# Agrobot_1_1.net
KiCad netlist of a schematic drawn in Altium Designer
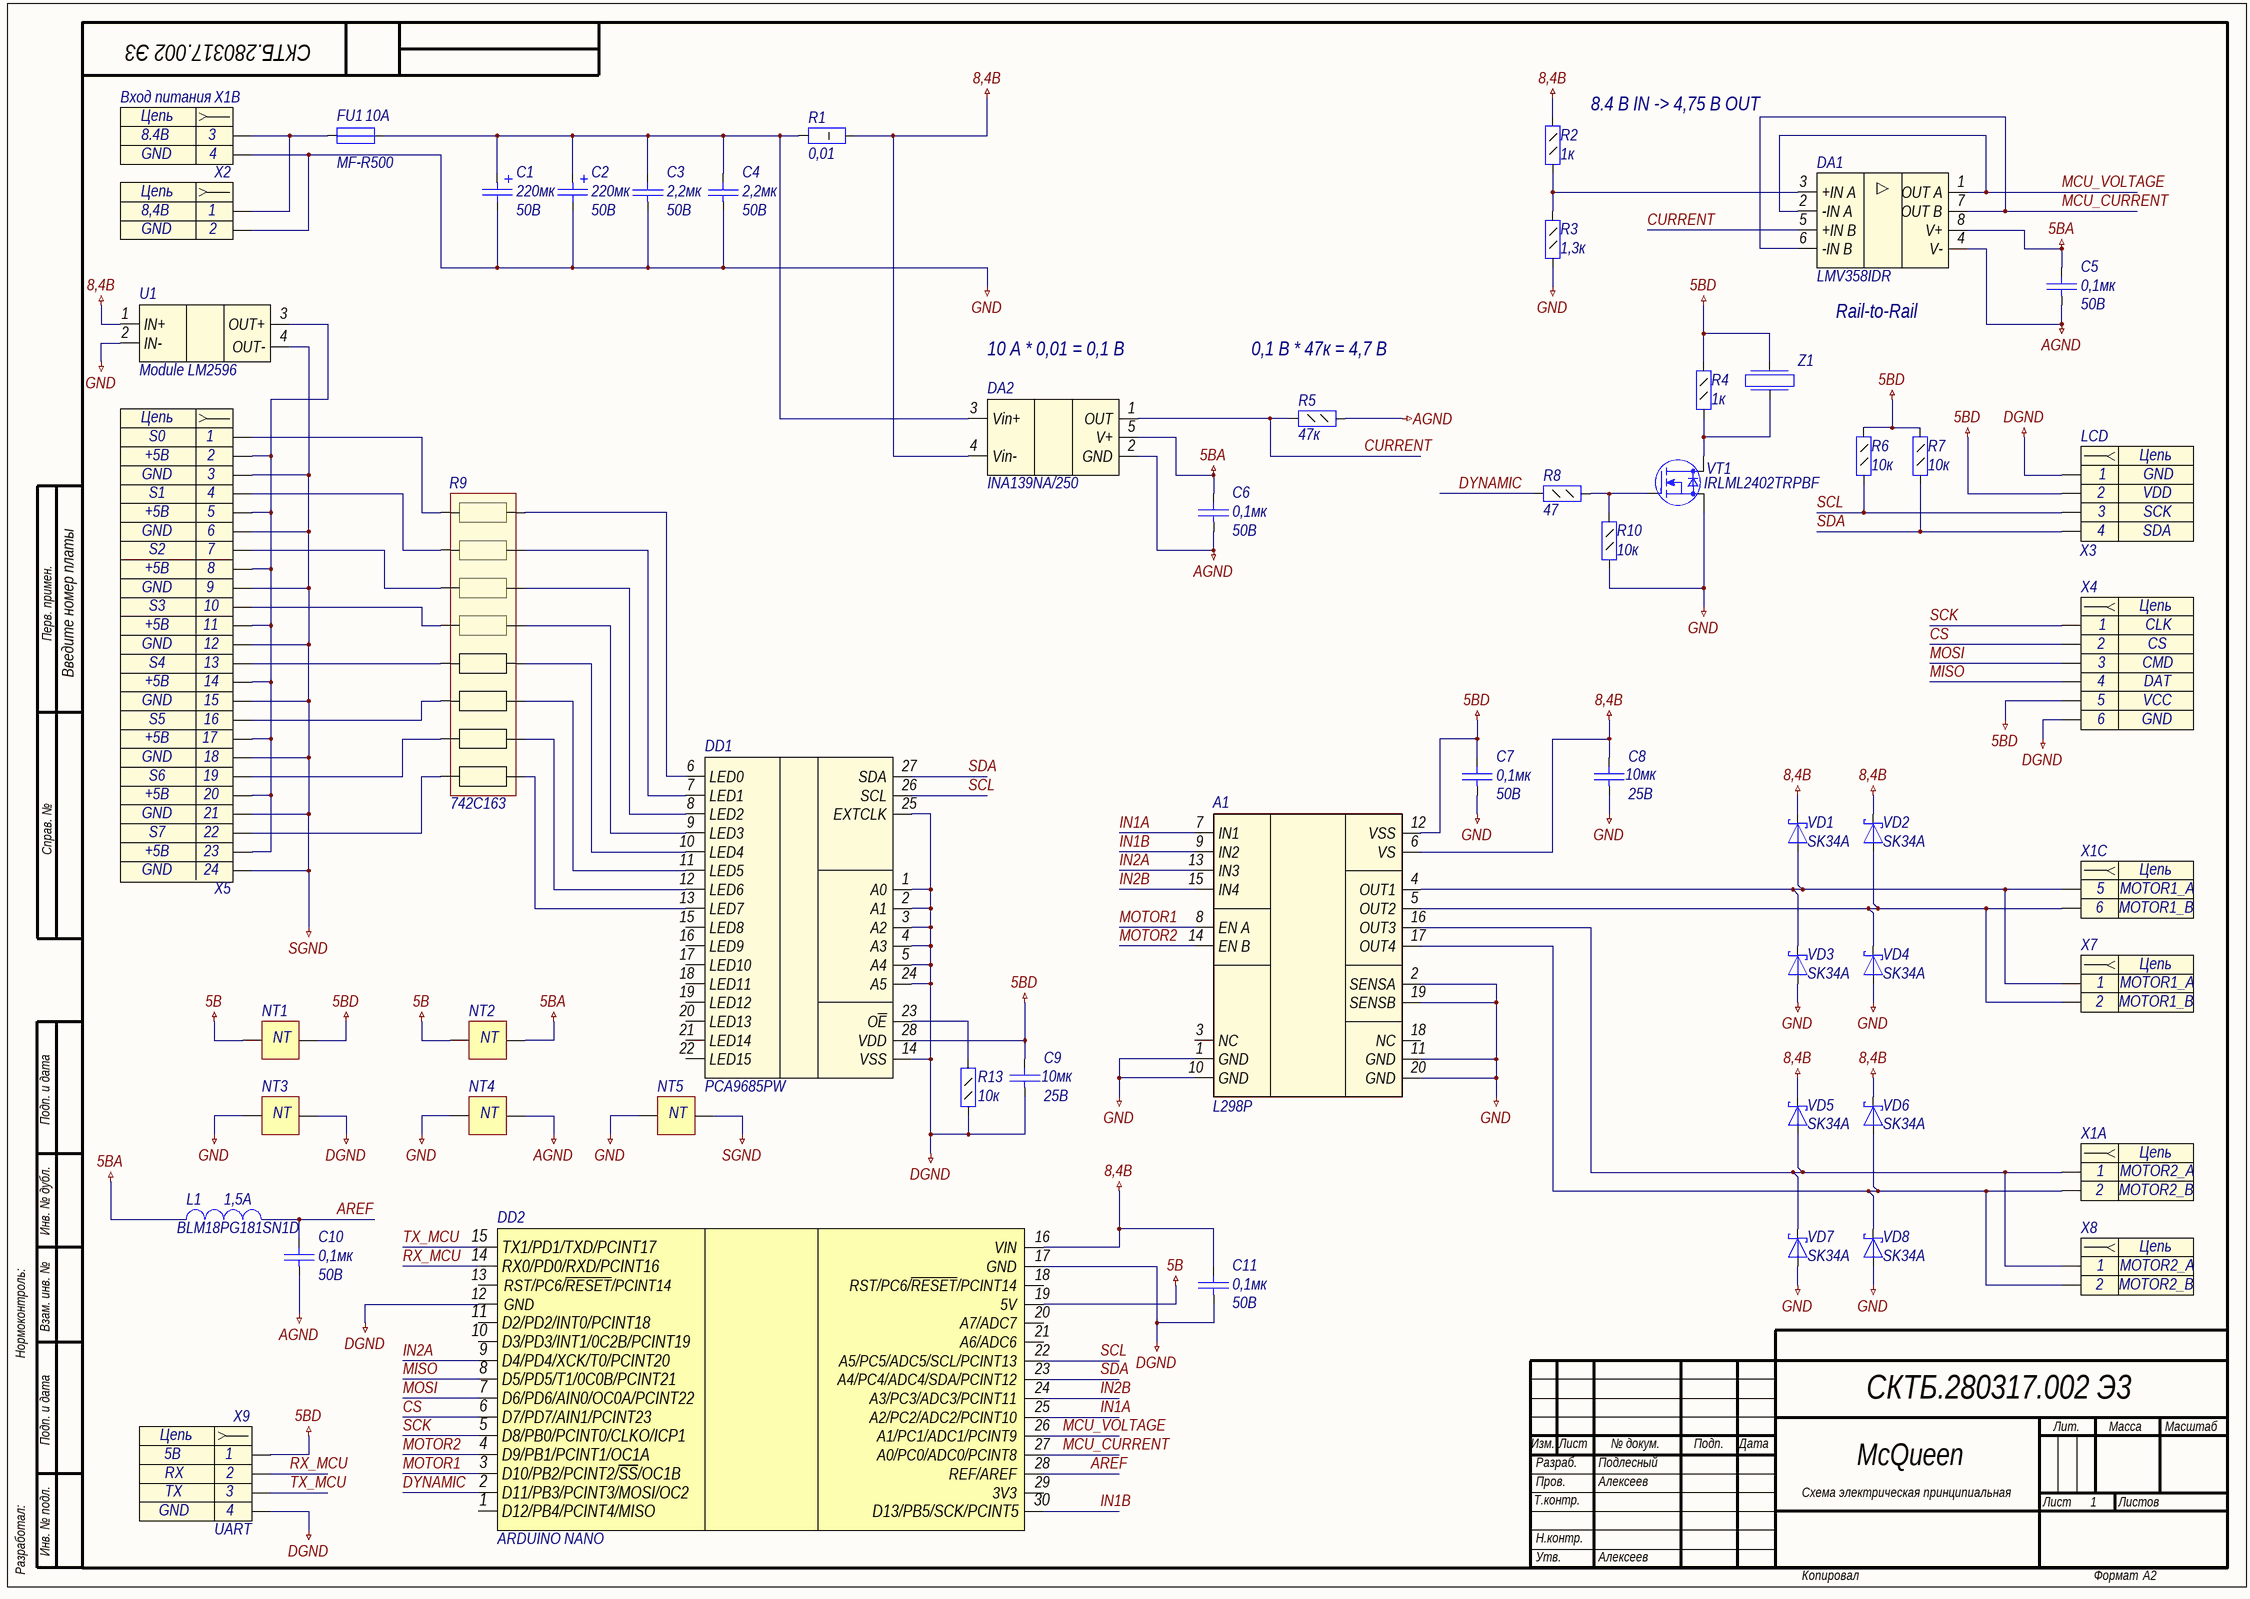
[diagram p0: Agrobot_1.1.SchDoc]

(export (version "E")
  (design (tool "Eeschema 10.0.6"))
  (components
    (comp (ref "A1")
      (value "L298P")
      (footprint "POWERSO20")
      (description "FULL BRIDGE DC MOTOR DRIVER")
      (libsource (lib "MOP44") (part "L298P"))
    )
    (comp (ref "C1")
      (value "220мк")
      (footprint "Cap_SMD_radial_polar(10x10.5)")
      (description "Конденсатор полярный")
      (fields
        (field (name "VOLTAGE") "50В")
        (field (name "PART NUMBER") "ECAP SMD")
        (field (name "Comment") "Capacitor_pol")
      )
      (libsource (lib "MOP44") (part "Capacitor_pol"))
    )
    (comp (ref "C2")
      (value "220мк")
      (footprint "Cap_SMD_radial_polar(10x10.5)")
      (description "Конденсатор полярный")
      (fields
        (field (name "VOLTAGE") "50В")
        (field (name "PART NUMBER") "ECAP SMD")
        (field (name "Comment") "Capacitor_pol")
      )
      (libsource (lib "MOP44") (part "Capacitor_pol"))
    )
    (comp (ref "C3")
      (value "2,2мк")
      (footprint "C0805")
      (description "Конденсатор")
      (fields
        (field (name "VOLTAGE") "50B")
        (field (name "PART NUMBER") "GRM21BR71E225K")
        (field (name "Comment") "Capacitor")
      )
      (libsource (lib "MOP44") (part "Capacitor"))
    )
    (comp (ref "C4")
      (value "2,2мк")
      (footprint "C0805")
      (description "Конденсатор")
      (fields
        (field (name "VOLTAGE") "50B")
        (field (name "PART NUMBER") "GRM21BR71E225K")
        (field (name "Comment") "Capacitor")
      )
      (libsource (lib "MOP44") (part "Capacitor"))
    )
    (comp (ref "C5")
      (value "0,1мк")
      (footprint "C0805")
      (description "Конденсатор")
      (fields
        (field (name "VOLTAGE") "50B")
        (field (name "PART NUMBER") "GRM21BR71E225K")
        (field (name "Comment") "Capacitor")
      )
      (libsource (lib "MOP44") (part "Capacitor"))
    )
    (comp (ref "C6")
      (value "0,1мк")
      (footprint "C0805")
      (description "Конденсатор")
      (fields
        (field (name "VOLTAGE") "50B")
        (field (name "PART NUMBER") "GRM21BR71E225K")
        (field (name "Comment") "Capacitor")
      )
      (libsource (lib "MOP44") (part "Capacitor"))
    )
    (comp (ref "C7")
      (value "0,1мк")
      (footprint "C0805")
      (description "Конденсатор")
      (fields
        (field (name "VOLTAGE") "50B")
        (field (name "PART NUMBER") "GRM21BR71E225K")
        (field (name "Comment") "Capacitor")
      )
      (libsource (lib "MOP44") (part "Capacitor"))
    )
    (comp (ref "C8")
      (value "10мк")
      (footprint "C1210")
      (description "Конденсатор")
      (fields
        (field (name "VOLTAGE") "25В")
        (field (name "PART NUMBER") "GRM32ER61A106K")
        (field (name "Comment") "Capacitor")
      )
      (libsource (lib "MOP44") (part "Capacitor"))
    )
    (comp (ref "C9")
      (value "10мк")
      (footprint "C1210")
      (description "Конденсатор")
      (fields
        (field (name "VOLTAGE") "25В")
        (field (name "PART NUMBER") "GRM32ER61A106K")
        (field (name "Comment") "Capacitor")
      )
      (libsource (lib "MOP44") (part "Capacitor"))
    )
    (comp (ref "C10")
      (value "0,1мк")
      (footprint "C0805")
      (description "Конденсатор")
      (fields
        (field (name "VOLTAGE") "50B")
        (field (name "PART NUMBER") "GRM21BR71E225K")
        (field (name "Comment") "Capacitor")
      )
      (libsource (lib "MOP44") (part "Capacitor"))
    )
    (comp (ref "C11")
      (value "0,1мк")
      (footprint "C0805")
      (description "Конденсатор")
      (fields
        (field (name "VOLTAGE") "50B")
        (field (name "PART NUMBER") "GRM21BR71E225K")
        (field (name "Comment") "Capacitor")
      )
      (libsource (lib "MOP44") (part "Capacitor"))
    )
    (comp (ref "DA1")
      (value "LMV358IDR")
      (footprint "SO8")
      (description "LOW-VOLTAGE RAIL-TO-RAIL OUTPUT OPERATIONAL AMPLIFIERS")
      (libsource (lib "MOP44") (part "LMV358IDR"))
    )
    (comp (ref "DA2")
      (value "INA139NA/250")
      (footprint "SOT23-5")
      (description "Измерительный датчик тока")
      (libsource (lib "MOP44") (part "INA139NA/250"))
    )
    (comp (ref "DD1")
      (value "PCA9685PW")
      (footprint "TSSOP28")
      (description "Драйвер светодиода, 16 выходов")
      (libsource (lib "MOP44") (part "PCA9685PW"))
    )
    (comp (ref "DD2")
      (value "ARDUINO NANO")
      (footprint "ARDUINO NANO")
      (description "Отладочная плата ATmega328")
      (libsource (lib "MOP44") (part "ARDUINO NANO"))
    )
    (comp (ref "FU1")
      (value "Fuse")
      (footprint "MF-R500")
      (description "Предохранитель")
      (fields (field (name "I TRIP") "10A") (field (name "PART NUMBER") "MF-R500"))
      (libsource (lib "MOP44") (part "Fuse"))
    )
    (comp (ref "L1")
      (value "Inductor")
      (footprint "L0603")
      (description "EMI Suppression Filter")
      (fields (field (name "PART NUMBER") "BLM18PG181SN1D") (field (name "RATED CURRENT") "1,5A"))
      (libsource (lib "MOP44") (part "Inductor"))
    )
    (comp (ref "NT1")
      (value "Pofigistor")
      (footprint "Pofigistor0603")
      (libsource (lib "MOP44") (part "Pofigistor"))
    )
    (comp (ref "NT2")
      (value "Pofigistor")
      (footprint "Pofigistor0603")
      (libsource (lib "MOP44") (part "Pofigistor"))
    )
    (comp (ref "NT3")
      (value "Pofigistor")
      (footprint "Pofigistor0603")
      (libsource (lib "MOP44") (part "Pofigistor"))
    )
    (comp (ref "NT4")
      (value "Pofigistor")
      (footprint "Pofigistor0603")
      (libsource (lib "MOP44") (part "Pofigistor"))
    )
    (comp (ref "NT5")
      (value "Pofigistor")
      (footprint "Pofigistor0603")
      (libsource (lib "MOP44") (part "Pofigistor"))
    )
    (comp (ref "R1")
      (value "0,01")
      (footprint "R2512")
      (description "Резистор")
      (fields (field (name "POWER") "1Вт") (field (name "Comment") "Resistor_1Вт"))
      (libsource (lib "MOP44") (part "Resistor_1Вт"))
    )
    (comp (ref "R2")
      (value "1к")
      (footprint "R0805")
      (description "Резистор")
      (fields (field (name "POWER") "0,125Вт") (field (name "Comment") "Resistor_0,125Вт"))
      (libsource (lib "MOP44") (part "Resistor_0,125Вт"))
    )
    (comp (ref "R3")
      (value "1,3к")
      (footprint "R0805")
      (description "Резистор")
      (fields (field (name "POWER") "0,125Вт") (field (name "Comment") "Resistor_0,125Вт"))
      (libsource (lib "MOP44") (part "Resistor_0,125Вт"))
    )
    (comp (ref "R4")
      (value "1к")
      (footprint "R0805")
      (description "Резистор")
      (fields (field (name "POWER") "0,125Вт") (field (name "Comment") "Resistor_0,125Вт"))
      (libsource (lib "MOP44") (part "Resistor_0,125Вт"))
    )
    (comp (ref "R5")
      (value "47к")
      (footprint "R0805")
      (description "Резистор")
      (fields (field (name "POWER") "0,125Вт") (field (name "Comment") "Resistor_0,125Вт"))
      (libsource (lib "") (part "Resistor_0,125Вт_1"))
    )
    (comp (ref "R6")
      (value "10к")
      (footprint "R0805")
      (description "Резистор")
      (fields (field (name "POWER") "0,125Вт") (field (name "Comment") "Resistor_0,125Вт"))
      (libsource (lib "MOP44") (part "Resistor_0,125Вт"))
    )
    (comp (ref "R7")
      (value "10к")
      (footprint "R0805")
      (description "Резистор")
      (fields (field (name "POWER") "0,125Вт") (field (name "Comment") "Resistor_0,125Вт"))
      (libsource (lib "MOP44") (part "Resistor_0,125Вт"))
    )
    (comp (ref "R8")
      (value "47")
      (footprint "R0805")
      (description "Резистор")
      (fields (field (name "POWER") "0,125Вт") (field (name "Comment") "Resistor_0,125Вт"))
      (libsource (lib "") (part "Resistor_0,125Вт_1"))
    )
    (comp (ref "R9")
      (value "742C163")
      (footprint "ZabugorLib:8xR1206")
      (description "Резисторная сборка")
      (libsource (lib "MOP44") (part "742C163"))
    )
    (comp (ref "R10")
      (value "10к")
      (footprint "R0805")
      (description "Резистор")
      (fields (field (name "POWER") "0,125Вт") (field (name "Comment") "Resistor_0,125Вт"))
      (libsource (lib "MOP44") (part "Resistor_0,125Вт"))
    )
    (comp (ref "R13")
      (value "10к")
      (footprint "R0805")
      (description "Резистор")
      (fields (field (name "POWER") "0,125Вт") (field (name "Comment") "Resistor_0,125Вт"))
      (libsource (lib "") (part "Resistor_0,125Вт_2"))
    )
    (comp (ref "U1")
      (value "Module LM2596")
      (footprint "module LM2596")
      (description "Low-Dropout Regulator for 5-V to 3.3-V Conversion")
      (libsource (lib "MOP44") (part "Module LM2596"))
    )
    (comp (ref "VD1")
      (value "DiodeSchottky")
      (footprint "SMA")
      (description "Диод Шоттки")
      (fields (field (name "PART NUMBER") "SK34A"))
      (libsource (lib "MOP44") (part "DiodeSchottky"))
    )
    (comp (ref "VD2")
      (value "DiodeSchottky")
      (footprint "SMA")
      (description "Диод Шоттки")
      (fields (field (name "PART NUMBER") "SK34A"))
      (libsource (lib "MOP44") (part "DiodeSchottky"))
    )
    (comp (ref "VD3")
      (value "DiodeSchottky")
      (footprint "SMA")
      (description "Диод Шоттки")
      (fields (field (name "PART NUMBER") "SK34A"))
      (libsource (lib "MOP44") (part "DiodeSchottky"))
    )
    (comp (ref "VD4")
      (value "DiodeSchottky")
      (footprint "SMA")
      (description "Диод Шоттки")
      (fields (field (name "PART NUMBER") "SK34A"))
      (libsource (lib "MOP44") (part "DiodeSchottky"))
    )
    (comp (ref "VD5")
      (value "DiodeSchottky")
      (footprint "SMA")
      (description "Диод Шоттки")
      (fields (field (name "PART NUMBER") "SK34A"))
      (libsource (lib "MOP44") (part "DiodeSchottky"))
    )
    (comp (ref "VD6")
      (value "DiodeSchottky")
      (footprint "SMA")
      (description "Диод Шоттки")
      (fields (field (name "PART NUMBER") "SK34A"))
      (libsource (lib "MOP44") (part "DiodeSchottky"))
    )
    (comp (ref "VD7")
      (value "DiodeSchottky")
      (footprint "SMA")
      (description "Диод Шоттки")
      (fields (field (name "PART NUMBER") "SK34A"))
      (libsource (lib "MOP44") (part "DiodeSchottky"))
    )
    (comp (ref "VD8")
      (value "DiodeSchottky")
      (footprint "SMA")
      (description "Диод Шоттки")
      (fields (field (name "PART NUMBER") "SK34A"))
      (libsource (lib "MOP44") (part "DiodeSchottky"))
    )
    (comp (ref "VT1")
      (value "N-MOSFET")
      (footprint "SOT23-3")
      (fields (field (name "PART NUMBER") "IRLML2402TRPBF"))
      (libsource (lib "MOP44") (part "N-MOSFET"))
    )
    (comp (ref "X1")
      (value "Вход питания")
      (footprint "ZabugorLib:DT-128V-6")
      (description "POWER")
      (libsource (lib "MOP44") (part "Header_6_motor"))
    )
    (comp (ref "X2")
      (value "Header_2_sct")
      (footprint "2HOLE_2.5")
      (description "Разъем - 2 конт. розетка")
      (libsource (lib "") (part "Header_2_sct_1"))
    )
    (comp (ref "X3")
      (value "LCD")
      (footprint "PLS-4HOLES")
      (description "Разъем - 4 конт. розетка")
      (libsource (lib "") (part "Header_4_sct_1"))
    )
    (comp (ref "X4")
      (value "Header_6_sct")
      (footprint "PSP_ANTENNA")
      (description "Разъем - 6 конт. розетка")
      (libsource (lib "MOP44") (part "Header_6_sct"))
    )
    (comp (ref "X5")
      (value "Header_24_sct")
      (footprint "PLS-24-3")
      (description "Разъем - 5 конт. розетка")
      (libsource (lib "MOP44") (part "Header_24_sct"))
    )
    (comp (ref "X7")
      (value "Header_2_sct")
      (footprint "2HOLE_2.5")
      (description "Разъем - 2 конт. розетка")
      (libsource (lib "MOP44") (part "Header_2_sct"))
    )
    (comp (ref "X8")
      (value "Header_2_sct")
      (footprint "2HOLE_2.5")
      (description "Разъем - 2 конт. розетка")
      (libsource (lib "MOP44") (part "Header_2_sct"))
    )
    (comp (ref "X9")
      (value "UART")
      (footprint "PLS-4HOLES")
      (description "Разъем - 4 конт. розетка")
      (libsource (lib "MOP44") (part "Header_4_sct"))
    )
    (comp (ref "Z1")
      (value "~")
      (footprint "Buzzer_9mm")
      (description "Пьезоизлучатель звуковой без генератора")
      (fields (field (name "PART NUMBER") "HC0905F"))
      (libsource (lib "MOP44") (part "Buzzer"))
    )
  )
  (nets
    (net (code "1") (name "/AREF") (class "Default")
      (node (ref "C10") (pin "2") (pinfunction "2_2") (pintype "passive"))
      (node (ref "DD2") (pin "28") (pinfunction "REF/AREF_28") (pintype "passive"))
      (node (ref "L1") (pin "2") (pinfunction "2_2") (pintype "passive"))
    )
    (net (code "2") (name "/CS") (class "Default")
      (node (ref "DD2") (pin "6") (pinfunction "D7/PD7/AIN1/PCINT23_6") (pintype "passive"))
      (node (ref "X4") (pin "2") (pinfunction "2_2") (pintype "passive"))
    )
    (net (code "3") (name "/CURRENT") (class "Default")
      (node (ref "DA1") (pin "5") (pinfunction "+IN_B_5") (pintype "passive"))
      (node (ref "DA2") (pin "1") (pinfunction "OUT_1") (pintype "power_in"))
      (node (ref "R5") (pin "2") (pinfunction "2_2") (pintype "passive"))
    )
    (net (code "4") (name "/DYNAMIC") (class "Default")
      (node (ref "DD2") (pin "2") (pinfunction "D11/PB3/PCINT3/MOSI/OC2_2") (pintype "passive"))
      (node (ref "R8") (pin "2") (pinfunction "2_2") (pintype "passive"))
    )
    (net (code "5") (name "/IN1A") (class "Default")
      (node (ref "A1") (pin "7") (pinfunction "IN1_7") (pintype "passive"))
      (node (ref "DD2") (pin "25") (pinfunction "A2/PC2/ADC2/PCINT10_25") (pintype "passive"))
    )
    (net (code "6") (name "/IN1B") (class "Default")
      (node (ref "A1") (pin "9") (pinfunction "IN2_9") (pintype "passive"))
      (node (ref "DD2") (pin "30") (pinfunction "D13/PB5/SCK/PCINT5_30") (pintype "passive"))
    )
    (net (code "7") (name "/IN2A") (class "Default")
      (node (ref "A1") (pin "13") (pinfunction "IN3_13") (pintype "passive"))
      (node (ref "DD2") (pin "9") (pinfunction "D4/PD4/XCK/T0/PCINT20_9") (pintype "passive"))
    )
    (net (code "8") (name "/IN2B") (class "Default")
      (node (ref "A1") (pin "15") (pinfunction "IN4_15") (pintype "passive"))
      (node (ref "DD2") (pin "24") (pinfunction "A3/PC3/ADC3/PCINT11_24") (pintype "passive"))
    )
    (net (code "9") (name "/MCU_CURRENT") (class "Default")
      (node (ref "DA1") (pin "6") (pinfunction "-IN_B_6") (pintype "passive"))
      (node (ref "DA1") (pin "7") (pinfunction "OUT_B_7") (pintype "passive"))
      (node (ref "DD2") (pin "27") (pinfunction "A0/PC0/ADC0/PCINT8_27") (pintype "passive"))
    )
    (net (code "10") (name "/MCU_VOLTAGE") (class "Default")
      (node (ref "DA1") (pin "1") (pinfunction "OUT_A_1") (pintype "passive"))
      (node (ref "DA1") (pin "2") (pinfunction "-IN_A_2") (pintype "passive"))
      (node (ref "DD2") (pin "26") (pinfunction "A1/PC1/ADC1/PCINT9_26") (pintype "passive"))
    )
    (net (code "11") (name "/MISO") (class "Default")
      (node (ref "DD2") (pin "8") (pinfunction "D5/PD5/T1/0C0B/PCINT21_8") (pintype "passive"))
      (node (ref "X4") (pin "4") (pinfunction "4_4") (pintype "passive"))
    )
    (net (code "12") (name "/MOSI") (class "Default")
      (node (ref "DD2") (pin "7") (pinfunction "D6/PD6/AIN0/OC0A/PCINT22_7") (pintype "passive"))
      (node (ref "X4") (pin "3") (pinfunction "3_3") (pintype "passive"))
    )
    (net (code "13") (name "/MOTOR1") (class "Default")
      (node (ref "A1") (pin "8") (pinfunction "EN_A_8") (pintype "passive"))
      (node (ref "DD2") (pin "3") (pinfunction "D10/PB2/PCINT2/~{SS}/OC1B_3") (pintype "passive"))
    )
    (net (code "14") (name "/MOTOR2") (class "Default")
      (node (ref "A1") (pin "14") (pinfunction "EN_B_14") (pintype "passive"))
      (node (ref "DD2") (pin "4") (pinfunction "D9/PB1/PCINT1/OC1A_4") (pintype "passive"))
    )
    (net (code "15") (name "/RX_MCU") (class "Default")
      (node (ref "DD2") (pin "14") (pinfunction "RX0/PD0/RXD/PCINT16_14") (pintype "passive"))
      (node (ref "X9") (pin "2") (pinfunction "2_2") (pintype "passive"))
    )
    (net (code "16") (name "/SCK") (class "Default")
      (node (ref "DD2") (pin "5") (pinfunction "D8/PB0/PCINT0/CLKO/ICP1_5") (pintype "passive"))
      (node (ref "X4") (pin "1") (pinfunction "1_1") (pintype "passive"))
    )
    (net (code "17") (name "/SCL") (class "Default")
      (node (ref "DD1") (pin "26") (pinfunction "SCL_26") (pintype "power_in"))
      (node (ref "DD2") (pin "22") (pinfunction "A5/PC5/ADC5/SCL/PCINT13_22") (pintype "passive"))
      (node (ref "R6") (pin "2") (pinfunction "2_2") (pintype "passive"))
      (node (ref "X3") (pin "3") (pinfunction "3_3") (pintype "passive"))
    )
    (net (code "18") (name "/SDA") (class "Default")
      (node (ref "DD1") (pin "27") (pinfunction "SDA_27") (pintype "power_in"))
      (node (ref "DD2") (pin "23") (pinfunction "A4/PC4/ADC4/SDA/PCINT12_23") (pintype "passive"))
      (node (ref "R7") (pin "2") (pinfunction "2_2") (pintype "passive"))
      (node (ref "X3") (pin "4") (pinfunction "4_4") (pintype "passive"))
    )
    (net (code "19") (name "/TX_MCU") (class "Default")
      (node (ref "DD2") (pin "15") (pinfunction "TX1/PD1/TXD/PCINT17_15") (pintype "passive"))
      (node (ref "X9") (pin "3") (pinfunction "3_3") (pintype "passive"))
    )
    (net (code "20") (name "5В") (class "Default")
      (node (ref "DD2") (pin "19") (pinfunction "5V_19") (pintype "passive"))
      (node (ref "NT1") (pin "1") (pinfunction "1_1") (pintype "passive"))
      (node (ref "NT2") (pin "1") (pinfunction "1_1") (pintype "passive"))
    )
    (net (code "21") (name "5ВA") (class "Default")
      (node (ref "C5") (pin "2") (pinfunction "2_2") (pintype "passive"))
      (node (ref "C6") (pin "2") (pinfunction "2_2") (pintype "passive"))
      (node (ref "DA1") (pin "8") (pinfunction "V+_8") (pintype "passive"))
      (node (ref "DA2") (pin "5") (pinfunction "V+_5") (pintype "power_in"))
      (node (ref "L1") (pin "1") (pinfunction "1_1") (pintype "passive"))
      (node (ref "NT2") (pin "2") (pinfunction "2_2") (pintype "passive"))
    )
    (net (code "22") (name "5ВD") (class "Default")
      (node (ref "A1") (pin "12") (pinfunction "VSS_12") (pintype "passive"))
      (node (ref "C7") (pin "2") (pinfunction "2_2") (pintype "passive"))
      (node (ref "C9") (pin "2") (pinfunction "2_2") (pintype "passive"))
      (node (ref "DD1") (pin "28") (pinfunction "VDD_28") (pintype "power_in"))
      (node (ref "NT1") (pin "2") (pinfunction "2_2") (pintype "passive"))
      (node (ref "R4") (pin "1") (pinfunction "1_1") (pintype "passive"))
      (node (ref "R6") (pin "1") (pinfunction "1_1") (pintype "passive"))
      (node (ref "R7") (pin "1") (pinfunction "1_1") (pintype "passive"))
      (node (ref "X3") (pin "2") (pinfunction "2_2") (pintype "passive"))
      (node (ref "X4") (pin "5") (pinfunction "5_5") (pintype "passive"))
      (node (ref "X9") (pin "1") (pinfunction "1_1") (pintype "passive"))
      (node (ref "Z1") (pin "2") (pinfunction "2_2") (pintype "passive"))
    )
    (net (code "23") (name "8,4В") (class "Default")
      (node (ref "A1") (pin "6") (pinfunction "VS_6") (pintype "passive"))
      (node (ref "C11") (pin "2") (pinfunction "2_2") (pintype "passive"))
      (node (ref "C8") (pin "2") (pinfunction "2_2") (pintype "passive"))
      (node (ref "DA2") (pin "4") (pinfunction "Vin-_4") (pintype "power_in"))
      (node (ref "DD2") (pin "16") (pinfunction "VIN_16") (pintype "passive"))
      (node (ref "R1") (pin "2") (pinfunction "5_2") (pintype "passive"))
      (node (ref "R2") (pin "1") (pinfunction "1_1") (pintype "passive"))
      (node (ref "U1") (pin "1") (pinfunction "IN+_1") (pintype "power_in"))
      (node (ref "VD1") (pin "1") (pinfunction "K_1") (pintype "passive"))
      (node (ref "VD2") (pin "1") (pinfunction "K_1") (pintype "passive"))
      (node (ref "VD5") (pin "1") (pinfunction "K_1") (pintype "passive"))
      (node (ref "VD6") (pin "1") (pinfunction "K_1") (pintype "passive"))
    )
    (net (code "24") (name "AGND") (class "Default")
      (node (ref "C10") (pin "1") (pinfunction "1_1") (pintype "passive"))
      (node (ref "C5") (pin "1") (pinfunction "1_1") (pintype "passive"))
      (node (ref "C6") (pin "1") (pinfunction "1_1") (pintype "passive"))
      (node (ref "DA1") (pin "4") (pinfunction "V-_4") (pintype "passive"))
      (node (ref "DA2") (pin "2") (pinfunction "GND_2") (pintype "power_in"))
      (node (ref "NT4") (pin "2") (pinfunction "2_2") (pintype "passive"))
      (node (ref "R5") (pin "1") (pinfunction "1_1") (pintype "passive"))
    )
    (net (code "25") (name "DGND") (class "Default")
      (node (ref "C11") (pin "1") (pinfunction "1_1") (pintype "passive"))
      (node (ref "C9") (pin "1") (pinfunction "1_1") (pintype "passive"))
      (node (ref "DD1") (pin "1") (pinfunction "A0_1") (pintype "power_in"))
      (node (ref "DD1") (pin "14") (pinfunction "VSS_14") (pintype "power_in"))
      (node (ref "DD1") (pin "2") (pinfunction "A1_2") (pintype "power_in"))
      (node (ref "DD1") (pin "24") (pinfunction "A5_24") (pintype "power_in"))
      (node (ref "DD1") (pin "25") (pinfunction "EXTCLK_25") (pintype "power_in"))
      (node (ref "DD1") (pin "3") (pinfunction "A2_3") (pintype "power_in"))
      (node (ref "DD1") (pin "4") (pinfunction "A3_4") (pintype "power_in"))
      (node (ref "DD1") (pin "5") (pinfunction "A4_5") (pintype "power_in"))
      (node (ref "DD2") (pin "12") (pinfunction "GND_12") (pintype "passive"))
      (node (ref "DD2") (pin "17") (pinfunction "GND_17") (pintype "passive"))
      (node (ref "NT3") (pin "2") (pinfunction "2_2") (pintype "passive"))
      (node (ref "R13") (pin "1") (pinfunction "1_1") (pintype "passive"))
      (node (ref "X3") (pin "1") (pinfunction "1_1") (pintype "passive"))
      (node (ref "X4") (pin "6") (pinfunction "6_6") (pintype "passive"))
      (node (ref "X9") (pin "4") (pinfunction "4_4") (pintype "passive"))
    )
    (net (code "26") (name "GND") (class "Default")
      (node (ref "A1") (pin "1") (pinfunction "GND_1") (pintype "passive"))
      (node (ref "A1") (pin "10") (pinfunction "GND_10") (pintype "passive"))
      (node (ref "A1") (pin "11") (pinfunction "GND_11") (pintype "passive"))
      (node (ref "A1") (pin "19") (pinfunction "SENSB_19") (pintype "passive"))
      (node (ref "A1") (pin "2") (pinfunction "SENSA_2") (pintype "passive"))
      (node (ref "A1") (pin "20") (pinfunction "GND_20") (pintype "passive"))
      (node (ref "C1") (pin "2") (pinfunction "2_2") (pintype "passive"))
      (node (ref "C2") (pin "2") (pinfunction "2_2") (pintype "passive"))
      (node (ref "C3") (pin "1") (pinfunction "1_1") (pintype "passive"))
      (node (ref "C4") (pin "1") (pinfunction "1_1") (pintype "passive"))
      (node (ref "C7") (pin "1") (pinfunction "1_1") (pintype "passive"))
      (node (ref "C8") (pin "1") (pinfunction "1_1") (pintype "passive"))
      (node (ref "NT3") (pin "1") (pinfunction "1_1") (pintype "passive"))
      (node (ref "NT4") (pin "1") (pinfunction "1_1") (pintype "passive"))
      (node (ref "NT5") (pin "1") (pinfunction "1_1") (pintype "passive"))
      (node (ref "R10") (pin "2") (pinfunction "2_2") (pintype "passive"))
      (node (ref "R3") (pin "2") (pinfunction "2_2") (pintype "passive"))
      (node (ref "U1") (pin "2") (pinfunction "IN-_2") (pintype "power_in"))
      (node (ref "VD3") (pin "2") (pinfunction "A_2") (pintype "passive"))
      (node (ref "VD4") (pin "2") (pinfunction "A_2") (pintype "passive"))
      (node (ref "VD7") (pin "2") (pinfunction "A_2") (pintype "passive"))
      (node (ref "VD8") (pin "2") (pinfunction "A_2") (pintype "passive"))
      (node (ref "VT1") (pin "2") (pinfunction "S_2") (pintype "passive"))
      (node (ref "X1") (pin "4") (pinfunction "4_4") (pintype "passive"))
      (node (ref "X2") (pin "2") (pinfunction "2_2") (pintype "passive"))
    )
    (net (code "27") (name "Net-(A1-OUT1)") (class "Default")
      (node (ref "A1") (pin "4") (pinfunction "OUT1_4") (pintype "passive"))
      (node (ref "VD1") (pin "2") (pinfunction "A_2") (pintype "passive"))
      (node (ref "VD3") (pin "1") (pinfunction "K_1") (pintype "passive"))
      (node (ref "X1") (pin "5") (pinfunction "5_5") (pintype "passive"))
      (node (ref "X7") (pin "1") (pinfunction "1_1") (pintype "passive"))
    )
    (net (code "28") (name "Net-(A1-OUT2)") (class "Default")
      (node (ref "A1") (pin "5") (pinfunction "OUT2_5") (pintype "passive"))
      (node (ref "VD2") (pin "2") (pinfunction "A_2") (pintype "passive"))
      (node (ref "VD4") (pin "1") (pinfunction "K_1") (pintype "passive"))
      (node (ref "X1") (pin "6") (pinfunction "6_6") (pintype "passive"))
      (node (ref "X7") (pin "2") (pinfunction "2_2") (pintype "passive"))
    )
    (net (code "29") (name "Net-(A1-OUT3)") (class "Default")
      (node (ref "A1") (pin "16") (pinfunction "OUT3_16") (pintype "passive"))
      (node (ref "VD5") (pin "2") (pinfunction "A_2") (pintype "passive"))
      (node (ref "VD7") (pin "1") (pinfunction "K_1") (pintype "passive"))
      (node (ref "X1") (pin "1") (pinfunction "1_1") (pintype "passive"))
      (node (ref "X8") (pin "1") (pinfunction "1_1") (pintype "passive"))
    )
    (net (code "30") (name "Net-(A1-OUT4)") (class "Default")
      (node (ref "A1") (pin "17") (pinfunction "OUT4_17") (pintype "passive"))
      (node (ref "VD6") (pin "2") (pinfunction "A_2") (pintype "passive"))
      (node (ref "VD8") (pin "1") (pinfunction "K_1") (pintype "passive"))
      (node (ref "X1") (pin "2") (pinfunction "2_2") (pintype "passive"))
      (node (ref "X8") (pin "2") (pinfunction "2_2") (pintype "passive"))
    )
    (net (code "31") (name "Net-(DA1-+IN_A)") (class "Default")
      (node (ref "DA1") (pin "3") (pinfunction "+IN_A_3") (pintype "passive"))
      (node (ref "R2") (pin "2") (pinfunction "2_2") (pintype "passive"))
      (node (ref "R3") (pin "1") (pinfunction "1_1") (pintype "passive"))
    )
    (net (code "32") (name "Net-(DA2-Vin+)") (class "Default")
      (node (ref "C1") (pin "1") (pinfunction "1_1") (pintype "passive"))
      (node (ref "C2") (pin "1") (pinfunction "1_1") (pintype "passive"))
      (node (ref "C3") (pin "2") (pinfunction "2_2") (pintype "passive"))
      (node (ref "C4") (pin "2") (pinfunction "2_2") (pintype "passive"))
      (node (ref "DA2") (pin "3") (pinfunction "Vin+_3") (pintype "power_in"))
      (node (ref "FU1") (pin "2") (pinfunction "2_2") (pintype "passive"))
      (node (ref "R1") (pin "1") (pinfunction "1_1") (pintype "passive"))
    )
    (net (code "33") (name "Net-(DD1-LED0)") (class "Default")
      (node (ref "DD1") (pin "6") (pinfunction "LED0_6") (pintype "power_in"))
      (node (ref "R9") (pin "2") (pinfunction "2_2") (pintype "passive"))
    )
    (net (code "34") (name "Net-(DD1-LED1)") (class "Default")
      (node (ref "DD1") (pin "7") (pinfunction "LED1_7") (pintype "power_in"))
      (node (ref "R9") (pin "4") (pinfunction "4_4") (pintype "passive"))
    )
    (net (code "35") (name "Net-(DD1-LED2)") (class "Default")
      (node (ref "DD1") (pin "8") (pinfunction "LED2_8") (pintype "power_in"))
      (node (ref "R9") (pin "6") (pinfunction "6_6") (pintype "passive"))
    )
    (net (code "36") (name "Net-(DD1-LED3)") (class "Default")
      (node (ref "DD1") (pin "9") (pinfunction "LED3_9") (pintype "power_in"))
      (node (ref "R9") (pin "8") (pinfunction "8_8") (pintype "passive"))
    )
    (net (code "37") (name "Net-(DD1-LED4)") (class "Default")
      (node (ref "DD1") (pin "10") (pinfunction "LED4_10") (pintype "power_in"))
      (node (ref "R9") (pin "10") (pinfunction "10_10") (pintype "passive"))
    )
    (net (code "38") (name "Net-(DD1-LED5)") (class "Default")
      (node (ref "DD1") (pin "11") (pinfunction "LED5_11") (pintype "power_in"))
      (node (ref "R9") (pin "12") (pinfunction "12_12") (pintype "passive"))
    )
    (net (code "39") (name "Net-(DD1-LED6)") (class "Default")
      (node (ref "DD1") (pin "12") (pinfunction "LED6_12") (pintype "power_in"))
      (node (ref "R9") (pin "14") (pinfunction "14_14") (pintype "passive"))
    )
    (net (code "40") (name "Net-(DD1-LED7)") (class "Default")
      (node (ref "DD1") (pin "13") (pinfunction "LED7_13") (pintype "power_in"))
      (node (ref "R9") (pin "16") (pinfunction "16_16") (pintype "passive"))
    )
    (net (code "41") (name "Net-(DD1-O~{E})") (class "Default")
      (node (ref "DD1") (pin "23") (pinfunction "O~{E}_23") (pintype "power_in"))
      (node (ref "R13") (pin "2") (pinfunction "2_2") (pintype "passive"))
    )
    (net (code "42") (name "Net-(FU1-Pad1)") (class "Default")
      (node (ref "FU1") (pin "1") (pinfunction "1_1") (pintype "passive"))
      (node (ref "X1") (pin "3") (pinfunction "3_3") (pintype "passive"))
      (node (ref "X2") (pin "1") (pinfunction "1_1") (pintype "passive"))
    )
    (net (code "43") (name "Net-(R9-Pad1)") (class "Default")
      (node (ref "R9") (pin "1") (pinfunction "1_1") (pintype "passive"))
      (node (ref "X5") (pin "1") (pinfunction "1_1") (pintype "passive"))
    )
    (net (code "44") (name "Net-(R9-Pad3)") (class "Default")
      (node (ref "R9") (pin "3") (pinfunction "3_3") (pintype "passive"))
      (node (ref "X5") (pin "4") (pinfunction "4_4") (pintype "passive"))
    )
    (net (code "45") (name "Net-(R9-Pad5)") (class "Default")
      (node (ref "R9") (pin "5") (pinfunction "5_5") (pintype "passive"))
      (node (ref "X5") (pin "7") (pinfunction "7_7") (pintype "passive"))
    )
    (net (code "46") (name "Net-(R9-Pad7)") (class "Default")
      (node (ref "R9") (pin "7") (pinfunction "7_7") (pintype "passive"))
      (node (ref "X5") (pin "10") (pinfunction "10_10") (pintype "passive"))
    )
    (net (code "47") (name "Net-(R9-Pad9)") (class "Default")
      (node (ref "R9") (pin "9") (pinfunction "9_9") (pintype "passive"))
      (node (ref "X5") (pin "13") (pinfunction "13_13") (pintype "passive"))
    )
    (net (code "48") (name "Net-(R9-Pad11)") (class "Default")
      (node (ref "R9") (pin "11") (pinfunction "11_11") (pintype "passive"))
      (node (ref "X5") (pin "16") (pinfunction "16_16") (pintype "passive"))
    )
    (net (code "49") (name "Net-(R9-Pad13)") (class "Default")
      (node (ref "R9") (pin "13") (pinfunction "13_13") (pintype "passive"))
      (node (ref "X5") (pin "19") (pinfunction "19_19") (pintype "passive"))
    )
    (net (code "50") (name "Net-(R9-Pad15)") (class "Default")
      (node (ref "R9") (pin "15") (pinfunction "15_15") (pintype "passive"))
      (node (ref "X5") (pin "22") (pinfunction "22_22") (pintype "passive"))
    )
    (net (code "51") (name "Net-(U1-OUT+)") (class "Default")
      (node (ref "U1") (pin "3") (pinfunction "OUT+_3") (pintype "power_in"))
      (node (ref "X5") (pin "11") (pinfunction "11_11") (pintype "passive"))
      (node (ref "X5") (pin "14") (pinfunction "14_14") (pintype "passive"))
      (node (ref "X5") (pin "17") (pinfunction "17_17") (pintype "passive"))
      (node (ref "X5") (pin "2") (pinfunction "2_2") (pintype "passive"))
      (node (ref "X5") (pin "20") (pinfunction "20_20") (pintype "passive"))
      (node (ref "X5") (pin "23") (pinfunction "23_23") (pintype "passive"))
      (node (ref "X5") (pin "5") (pinfunction "5_5") (pintype "passive"))
      (node (ref "X5") (pin "8") (pinfunction "8_8") (pintype "passive"))
    )
    (net (code "52") (name "Net-(VT1-D)") (class "Default")
      (node (ref "R4") (pin "2") (pinfunction "2_2") (pintype "passive"))
      (node (ref "VT1") (pin "3") (pinfunction "D_3") (pintype "passive"))
      (node (ref "Z1") (pin "1") (pinfunction "1_1") (pintype "passive"))
    )
    (net (code "53") (name "Net-(VT1-G)") (class "Default")
      (node (ref "R10") (pin "1") (pinfunction "1_1") (pintype "passive"))
      (node (ref "R8") (pin "1") (pinfunction "1_1") (pintype "passive"))
      (node (ref "VT1") (pin "1") (pinfunction "G_1") (pintype "passive"))
    )
    (net (code "54") (name "SGND") (class "Default")
      (node (ref "NT5") (pin "2") (pinfunction "2_2") (pintype "passive"))
      (node (ref "U1") (pin "4") (pinfunction "OUT-_4") (pintype "power_in"))
      (node (ref "X5") (pin "12") (pinfunction "12_12") (pintype "passive"))
      (node (ref "X5") (pin "15") (pinfunction "15_15") (pintype "passive"))
      (node (ref "X5") (pin "18") (pinfunction "18_18") (pintype "passive"))
      (node (ref "X5") (pin "21") (pinfunction "21_21") (pintype "passive"))
      (node (ref "X5") (pin "24") (pinfunction "24_24") (pintype "passive"))
      (node (ref "X5") (pin "3") (pinfunction "3_3") (pintype "passive"))
      (node (ref "X5") (pin "6") (pinfunction "6_6") (pintype "passive"))
      (node (ref "X5") (pin "9") (pinfunction "9_9") (pintype "passive"))
    )
    (net (code "55") (name "unconnected-(A1-NC-Pad3)") (class "Default")
      (node (ref "A1") (pin "3") (pinfunction "NC_3") (pintype "passive"))
    )
    (net (code "56") (name "unconnected-(A1-NC-Pad18)") (class "Default")
      (node (ref "A1") (pin "18") (pinfunction "NC_18") (pintype "passive"))
    )
    (net (code "57") (name "unconnected-(DD1-LED8-Pad15)") (class "Default")
      (node (ref "DD1") (pin "15") (pinfunction "LED8_15") (pintype "power_in"))
    )
    (net (code "58") (name "unconnected-(DD1-LED9-Pad16)") (class "Default")
      (node (ref "DD1") (pin "16") (pinfunction "LED9_16") (pintype "power_in"))
    )
    (net (code "59") (name "unconnected-(DD1-LED10-Pad17)") (class "Default")
      (node (ref "DD1") (pin "17") (pinfunction "LED10_17") (pintype "power_in"))
    )
    (net (code "60") (name "unconnected-(DD1-LED11-Pad18)") (class "Default")
      (node (ref "DD1") (pin "18") (pinfunction "LED11_18") (pintype "power_in"))
    )
    (net (code "61") (name "unconnected-(DD1-LED12-Pad19)") (class "Default")
      (node (ref "DD1") (pin "19") (pinfunction "LED12_19") (pintype "power_in"))
    )
    (net (code "62") (name "unconnected-(DD1-LED13-Pad20)") (class "Default")
      (node (ref "DD1") (pin "20") (pinfunction "LED13_20") (pintype "power_in"))
    )
    (net (code "63") (name "unconnected-(DD1-LED14-Pad21)") (class "Default")
      (node (ref "DD1") (pin "21") (pinfunction "LED14_21") (pintype "power_in"))
    )
    (net (code "64") (name "unconnected-(DD1-LED15-Pad22)") (class "Default")
      (node (ref "DD1") (pin "22") (pinfunction "LED15_22") (pintype "power_in"))
    )
    (net (code "65") (name "unconnected-(DD2-3V3-Pad29)") (class "Default")
      (node (ref "DD2") (pin "29") (pinfunction "3V3_29") (pintype "passive"))
    )
    (net (code "66") (name "unconnected-(DD2-A6{slash}ADC6-Pad21)") (class "Default")
      (node (ref "DD2") (pin "21") (pinfunction "A6/ADC6_21") (pintype "passive"))
    )
    (net (code "67") (name "unconnected-(DD2-A7{slash}ADC7-Pad20)") (class "Default")
      (node (ref "DD2") (pin "20") (pinfunction "A7/ADC7_20") (pintype "passive"))
    )
    (net (code "68") (name "unconnected-(DD2-D2{slash}PD2{slash}INT0{slash}PCINT18-Pad11)") (class "Default")
      (node (ref "DD2") (pin "11") (pinfunction "D2/PD2/INT0/PCINT18_11") (pintype "passive"))
    )
    (net (code "69") (name "unconnected-(DD2-D3{slash}PD3{slash}INT1{slash}0C2B{slash}PCINT19-Pad10)") (class "Default")
      (node (ref "DD2") (pin "10") (pinfunction "D3/PD3/INT1/0C2B/PCINT19_10") (pintype "passive"))
    )
    (net (code "70") (name "unconnected-(DD2-D12{slash}PB4{slash}PCINT4{slash}MISO-Pad1)") (class "Default")
      (node (ref "DD2") (pin "1") (pinfunction "D12/PB4/PCINT4/MISO_1") (pintype "passive"))
    )
    (net (code "71") (name "unconnected-(DD2-RST{slash}PC6{slash}~{RESET}{slash}PCINT14-Pad13)") (class "Default")
      (node (ref "DD2") (pin "13") (pinfunction "RST/PC6/~{RESET}/PCINT14_13") (pintype "passive"))
    )
    (net (code "72") (name "unconnected-(DD2-RST{slash}PC6{slash}~{RESET}{slash}PCINT14-Pad18)") (class "Default")
      (node (ref "DD2") (pin "18") (pinfunction "RST/PC6/~{RESET}/PCINT14_18") (pintype "passive"))
    )
  )
)
